# SCH_microprocessor-8085_2025-05-18.net
KiCad netlist of a schematic drawn in EasyEDA
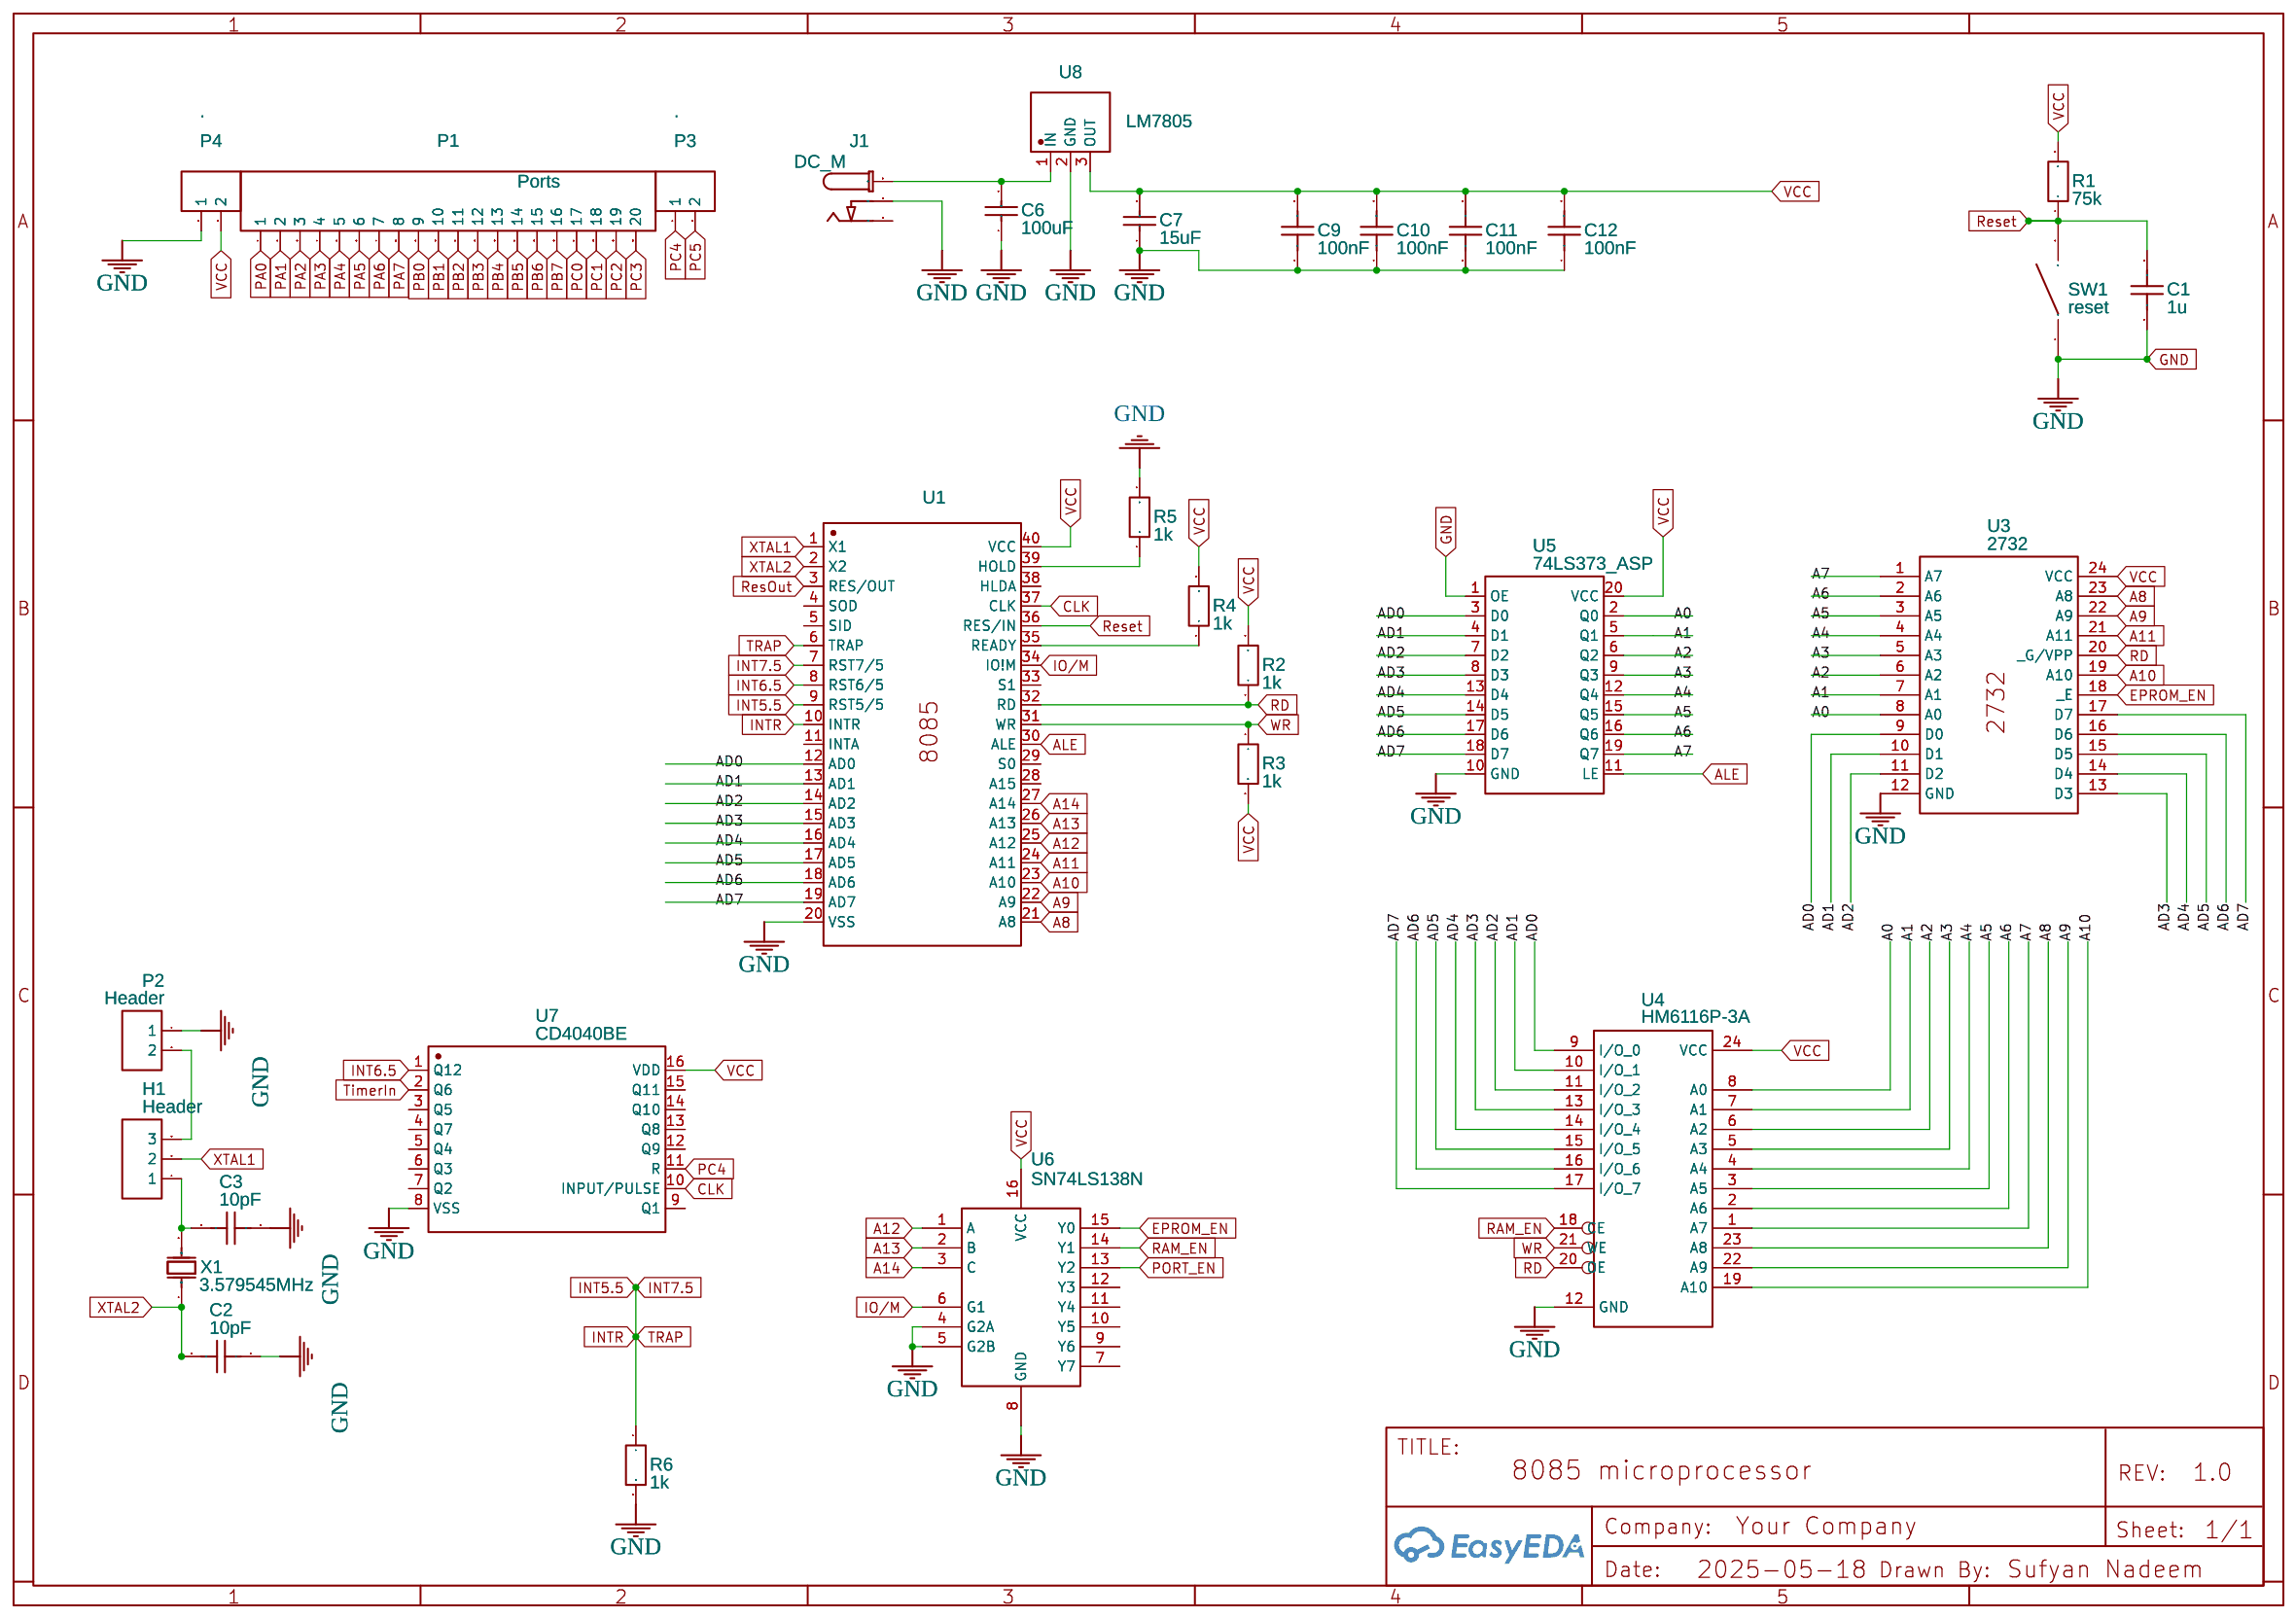
[diagram p0: schematic sheet]

(export (version "E")
  (design (tool "Eeschema 10.0.6"))
  (components
    (comp (ref "C1") (value "1u") (libsource (lib "") (part "Cap_RAD-0.1_US")))
    (comp (ref "C2")
      (value "10pF")
      (fields (field (name "Manufacturer Part") "CC4-0805N100 J500") (field (name "Manufacturer") "ReliaPro"))
      (libsource (lib "") (part "CC4-0805N100 J500"))
    )
    (comp (ref "C3")
      (value "10pF")
      (fields (field (name "Manufacturer Part") "CC4-0805N100 J500") (field (name "Manufacturer") "ReliaPro"))
      (libsource (lib "") (part "CC4-0805N100 J500"))
    )
    (comp (ref "C6")
      (value "100uF")
      (fields (field (name "Manufacturer Part") "Capacitor15nf100v") (field (name "Manufacturer") "ReliaPro"))
      (libsource (lib "") (part "CAPACITOR15NF100V"))
    )
    (comp (ref "C7")
      (value "15uF")
      (fields (field (name "Manufacturer Part") "Capacitor15nf100v") (field (name "Manufacturer") "ReliaPro"))
      (libsource (lib "") (part "CAPACITOR15NF100V"))
    )
    (comp (ref "C9")
      (value "100nF")
      (fields (field (name "Manufacturer Part") "CT4-0805B104K500F3") (field (name "Manufacturer") "FH"))
      (libsource (lib "") (part "CT4-0805B104K500F3"))
    )
    (comp (ref "C10")
      (value "100nF")
      (fields (field (name "Manufacturer Part") "CT4-0805B104K500F3") (field (name "Manufacturer") "FH"))
      (libsource (lib "") (part "CT4-0805B104K500F3"))
    )
    (comp (ref "C11")
      (value "100nF")
      (fields (field (name "Manufacturer Part") "CT4-0805B104K500F3") (field (name "Manufacturer") "FH"))
      (libsource (lib "") (part "CT4-0805B104K500F3"))
    )
    (comp (ref "C12")
      (value "100nF")
      (fields (field (name "Manufacturer Part") "CT4-0805B104K500F3") (field (name "Manufacturer") "FH"))
      (libsource (lib "") (part "CT4-0805B104K500F3"))
    )
    (comp (ref "H1")
      (value "Header")
      (fields (field (name "Manufacturer Part") "Header2.54mm 1*3P") (field (name "Manufacturer") "BOOMELE"))
      (libsource (lib "") (part "Unknown_50_-260"))
    )
    (comp (ref "J1") (value "DC_M") (libsource (lib "") (part "Unknown_410_-745")))
    (comp (ref "P1")
      (value "Ports")
      (fields
        (field (name "Manufacturer Part") "2.54mm 1*20P Female header")
        (field (name "Manufacturer") "BOOMELE")
      )
      (libsource (lib "") (part "Unknown_200_-740"))
    )
    (comp (ref "P2")
      (value "Header")
      (fields (field (name "Manufacturer Part") "2.54-1*2PFemale") (field (name "Manufacturer") "BOOMELE"))
      (libsource (lib "") (part "Header-Female-2.54_1x2"))
    )
    (comp (ref "P3")
      (value ".")
      (fields (field (name "Manufacturer Part") "2.54-1*2PFemale") (field (name "Manufacturer") "BOOMELE"))
      (libsource (lib "") (part "Unknown_320_-745"))
    )
    (comp (ref "P4")
      (value ".")
      (fields (field (name "Manufacturer Part") "2.54-1*2PFemale") (field (name "Manufacturer") "BOOMELE"))
      (libsource (lib "") (part "Unknown_80_-745"))
    )
    (comp (ref "R1") (value "75k") (libsource (lib "") (part "Res_AXIAL-0.3(1/8W)_EU")))
    (comp (ref "R2") (value "1k") (libsource (lib "") (part "Res_AXIAL-0.3(1/8W)_EU")))
    (comp (ref "R3") (value "1k") (libsource (lib "") (part "Res_AXIAL-0.3(1/8W)_EU_1")))
    (comp (ref "R4") (value "1k") (libsource (lib "") (part "Res_AXIAL-0.3(1/8W)_EU")))
    (comp (ref "R5") (value "1k") (libsource (lib "") (part "Res_AXIAL-0.3(1/8W)_EU")))
    (comp (ref "R6") (value "1k") (libsource (lib "") (part "Res_AXIAL-0.3(1/8W)_EU_1")))
    (comp (ref "SW1")
      (value "reset")
      (fields (field (name "Manufacturer Part") "EVQ22705R") (field (name "Manufacturer") "PANASONIC"))
      (libsource (lib "") (part "Unknown_1015_-700"))
    )
    (comp (ref "U1") (value "8085_ASP") (libsource (lib "") (part "Unknown_440_-475")))
    (comp (ref "U3") (value "2732") (libsource (lib "") (part "Unknown_945_-565")))
    (comp (ref "U4")
      (value "HM6116P-3A")
      (fields (field (name "Manufacturer Part") "HM6116P-3"))
      (libsource (lib "") (part "HM6116P-3A"))
    )
    (comp (ref "U5") (value "74LS373_ASP") (libsource (lib "") (part "Unknown_725_-555")))
    (comp (ref "U6")
      (value "SN74LS138N")
      (fields (field (name "Manufacturer") "Texas Instruments"))
      (libsource (lib "") (part "Unknown_490_-185"))
    )
    (comp (ref "U7")
      (value "CD4040BE")
      (fields (field (name "Manufacturer") "TI"))
      (libsource (lib "") (part "Unknown_250_-270"))
    )
    (comp (ref "U8")
      (value "LM7805")
      (fields
        (field (name "Manufacturer Part") "LM7805AL-TA3-T")
        (field (name "Manufacturer") "Unisonic Tech")
      )
      (libsource (lib "") (part "Unknown_515_-785"))
    )
    (comp (ref "X1")
      (value "3.579545MHz")
      (fields
        (field (name "Manufacturer Part") "XIHCELNANF-3.579545M")
        (field (name "Manufacturer") "TAITIEN Elec")
      )
      (libsource (lib "") (part "XIHCELNANF-3.579545M"))
    )
  )
  (nets
    (net (code "1") (name "/A0") (class "Default")
      (node (ref "U3") (pin "8") (pinfunction "A0_8") (pintype "unspecified"))
      (node (ref "U4") (pin "8") (pinfunction "A0_8") (pintype "input"))
      (node (ref "U5") (pin "2") (pinfunction "Q0_2") (pintype "unspecified"))
    )
    (net (code "2") (name "/A1") (class "Default")
      (node (ref "U3") (pin "7") (pinfunction "A1_7") (pintype "unspecified"))
      (node (ref "U4") (pin "7") (pinfunction "A1_7") (pintype "input"))
      (node (ref "U5") (pin "5") (pinfunction "Q1_5") (pintype "unspecified"))
    )
    (net (code "3") (name "/A2") (class "Default")
      (node (ref "U3") (pin "6") (pinfunction "A2_6") (pintype "unspecified"))
      (node (ref "U4") (pin "6") (pinfunction "A2_6") (pintype "input"))
      (node (ref "U5") (pin "6") (pinfunction "Q2_6") (pintype "unspecified"))
    )
    (net (code "4") (name "/A3") (class "Default")
      (node (ref "U3") (pin "5") (pinfunction "A3_5") (pintype "unspecified"))
      (node (ref "U4") (pin "5") (pinfunction "A3_5") (pintype "input"))
      (node (ref "U5") (pin "9") (pinfunction "Q3_9") (pintype "unspecified"))
    )
    (net (code "5") (name "/A4") (class "Default")
      (node (ref "U3") (pin "4") (pinfunction "A4_4") (pintype "unspecified"))
      (node (ref "U4") (pin "4") (pinfunction "A4_4") (pintype "input"))
      (node (ref "U5") (pin "12") (pinfunction "Q4_12") (pintype "unspecified"))
    )
    (net (code "6") (name "/A5") (class "Default")
      (node (ref "U3") (pin "3") (pinfunction "A5_3") (pintype "unspecified"))
      (node (ref "U4") (pin "3") (pinfunction "A5_3") (pintype "input"))
      (node (ref "U5") (pin "15") (pinfunction "Q5_15") (pintype "unspecified"))
    )
    (net (code "7") (name "/A6") (class "Default")
      (node (ref "U3") (pin "2") (pinfunction "A6_2") (pintype "unspecified"))
      (node (ref "U4") (pin "2") (pinfunction "A6_2") (pintype "input"))
      (node (ref "U5") (pin "16") (pinfunction "Q6_16") (pintype "unspecified"))
    )
    (net (code "8") (name "/A7") (class "Default")
      (node (ref "U3") (pin "1") (pinfunction "A7_1") (pintype "unspecified"))
      (node (ref "U4") (pin "1") (pinfunction "A7_1") (pintype "input"))
      (node (ref "U5") (pin "19") (pinfunction "Q7_19") (pintype "unspecified"))
    )
    (net (code "9") (name "/AD0") (class "Default")
      (node (ref "U1") (pin "12") (pinfunction "AD0_12") (pintype "unspecified"))
      (node (ref "U3") (pin "9") (pinfunction "D0_9") (pintype "unspecified"))
      (node (ref "U4") (pin "9") (pinfunction "I/O_0_9") (pintype "bidirectional"))
      (node (ref "U5") (pin "3") (pinfunction "D0_3") (pintype "unspecified"))
    )
    (net (code "10") (name "/AD1") (class "Default")
      (node (ref "U1") (pin "13") (pinfunction "AD1_13") (pintype "unspecified"))
      (node (ref "U3") (pin "10") (pinfunction "D1_10") (pintype "unspecified"))
      (node (ref "U4") (pin "10") (pinfunction "I/O_1_10") (pintype "bidirectional"))
      (node (ref "U5") (pin "4") (pinfunction "D1_4") (pintype "unspecified"))
    )
    (net (code "11") (name "/AD2") (class "Default")
      (node (ref "U1") (pin "14") (pinfunction "AD2_14") (pintype "unspecified"))
      (node (ref "U3") (pin "11") (pinfunction "D2_11") (pintype "unspecified"))
      (node (ref "U4") (pin "11") (pinfunction "I/O_2_11") (pintype "bidirectional"))
      (node (ref "U5") (pin "7") (pinfunction "D2_7") (pintype "unspecified"))
    )
    (net (code "12") (name "/AD3") (class "Default")
      (node (ref "U1") (pin "15") (pinfunction "AD3_15") (pintype "unspecified"))
      (node (ref "U3") (pin "13") (pinfunction "D3_13") (pintype "unspecified"))
      (node (ref "U4") (pin "13") (pinfunction "I/O_3_13") (pintype "bidirectional"))
      (node (ref "U5") (pin "8") (pinfunction "D3_8") (pintype "unspecified"))
    )
    (net (code "13") (name "/AD4") (class "Default")
      (node (ref "U1") (pin "16") (pinfunction "AD4_16") (pintype "unspecified"))
      (node (ref "U3") (pin "14") (pinfunction "D4_14") (pintype "unspecified"))
      (node (ref "U4") (pin "14") (pinfunction "I/O_4_14") (pintype "bidirectional"))
      (node (ref "U5") (pin "13") (pinfunction "D4_13") (pintype "unspecified"))
    )
    (net (code "14") (name "/AD5") (class "Default")
      (node (ref "U1") (pin "17") (pinfunction "AD5_17") (pintype "unspecified"))
      (node (ref "U3") (pin "15") (pinfunction "D5_15") (pintype "unspecified"))
      (node (ref "U4") (pin "15") (pinfunction "I/O_5_15") (pintype "bidirectional"))
      (node (ref "U5") (pin "14") (pinfunction "D5_14") (pintype "unspecified"))
    )
    (net (code "15") (name "/AD6") (class "Default")
      (node (ref "U1") (pin "18") (pinfunction "AD6_18") (pintype "unspecified"))
      (node (ref "U3") (pin "16") (pinfunction "D6_16") (pintype "unspecified"))
      (node (ref "U4") (pin "16") (pinfunction "I/O_6_16") (pintype "bidirectional"))
      (node (ref "U5") (pin "17") (pinfunction "D6_17") (pintype "unspecified"))
    )
    (net (code "16") (name "/AD7") (class "Default")
      (node (ref "U1") (pin "19") (pinfunction "AD7_19") (pintype "unspecified"))
      (node (ref "U3") (pin "17") (pinfunction "D7_17") (pintype "unspecified"))
      (node (ref "U4") (pin "17") (pinfunction "I/O_7_17") (pintype "bidirectional"))
      (node (ref "U5") (pin "18") (pinfunction "D7_18") (pintype "unspecified"))
    )
    (net (code "17") (name "A8") (class "Default")
      (node (ref "U1") (pin "21") (pinfunction "A8_21") (pintype "unspecified"))
      (node (ref "U3") (pin "23") (pinfunction "A8_23") (pintype "unspecified"))
      (node (ref "U4") (pin "23") (pinfunction "A8_23") (pintype "input"))
    )
    (net (code "18") (name "A9") (class "Default")
      (node (ref "U1") (pin "22") (pinfunction "A9_22") (pintype "unspecified"))
      (node (ref "U3") (pin "22") (pinfunction "A9_22") (pintype "unspecified"))
      (node (ref "U4") (pin "22") (pinfunction "A9_22") (pintype "input"))
    )
    (net (code "19") (name "A10") (class "Default")
      (node (ref "U1") (pin "23") (pinfunction "A10_23") (pintype "unspecified"))
      (node (ref "U3") (pin "19") (pinfunction "A10_19") (pintype "unspecified"))
      (node (ref "U4") (pin "19") (pinfunction "A10_19") (pintype "input"))
    )
    (net (code "20") (name "A11") (class "Default")
      (node (ref "U1") (pin "24") (pinfunction "A11_24") (pintype "unspecified"))
      (node (ref "U3") (pin "21") (pinfunction "A11_21") (pintype "unspecified"))
    )
    (net (code "21") (name "A12") (class "Default")
      (node (ref "U1") (pin "25") (pinfunction "A12_25") (pintype "unspecified"))
      (node (ref "U6") (pin "1") (pinfunction "A_1") (pintype "unspecified"))
    )
    (net (code "22") (name "A13") (class "Default")
      (node (ref "U1") (pin "26") (pinfunction "A13_26") (pintype "unspecified"))
      (node (ref "U6") (pin "2") (pinfunction "B_2") (pintype "unspecified"))
    )
    (net (code "23") (name "A14") (class "Default")
      (node (ref "U1") (pin "27") (pinfunction "A14_27") (pintype "unspecified"))
      (node (ref "U6") (pin "3") (pinfunction "C_3") (pintype "unspecified"))
    )
    (net (code "24") (name "ALE") (class "Default")
      (node (ref "U1") (pin "30") (pinfunction "ALE_30") (pintype "unspecified"))
      (node (ref "U5") (pin "11") (pinfunction "LE_11") (pintype "unspecified"))
    )
    (net (code "25") (name "CLK") (class "Default")
      (node (ref "U1") (pin "37") (pinfunction "CLK_37") (pintype "unspecified"))
      (node (ref "U7") (pin "10") (pinfunction "INPUT/PULSE_10") (pintype "unspecified"))
    )
    (net (code "26") (name "EPROM_EN") (class "Default")
      (node (ref "U3") (pin "18") (pinfunction "_E_18") (pintype "unspecified"))
      (node (ref "U6") (pin "15") (pinfunction "Y0_15") (pintype "unspecified"))
    )
    (net (code "27") (name "GND") (class "Default")
      (node (ref "C1") (pin "1") (pinfunction "1_1") (pintype "unspecified"))
      (node (ref "C10") (pin "1") (pinfunction "1_1") (pintype "unspecified"))
      (node (ref "C11") (pin "1") (pinfunction "1_1") (pintype "unspecified"))
      (node (ref "C12") (pin "1") (pinfunction "1_1") (pintype "unspecified"))
      (node (ref "C2") (pin "1") (pinfunction "1_1") (pintype "unspecified"))
      (node (ref "C3") (pin "1") (pinfunction "1_1") (pintype "unspecified"))
      (node (ref "C6") (pin "1") (pinfunction "1_1") (pintype "input"))
      (node (ref "C7") (pin "1") (pinfunction "1_1") (pintype "input"))
      (node (ref "C9") (pin "1") (pinfunction "1_1") (pintype "unspecified"))
      (node (ref "J1") (pin "P2") (pinfunction "P3_P2") (pintype "unspecified"))
      (node (ref "P2") (pin "1") (pinfunction "1_1") (pintype "input"))
      (node (ref "P4") (pin "1") (pinfunction "1_1") (pintype "input"))
      (node (ref "R5") (pin "2") (pinfunction "2_2") (pintype "unspecified"))
      (node (ref "R6") (pin "2") (pinfunction "2_2") (pintype "unspecified"))
      (node (ref "SW1") (pin "1") (pinfunction "1_1") (pintype "input"))
      (node (ref "U1") (pin "20") (pinfunction "VSS_20") (pintype "unspecified"))
      (node (ref "U3") (pin "12") (pinfunction "GND_12") (pintype "unspecified"))
      (node (ref "U4") (pin "12") (pinfunction "GND_12") (pintype "passive"))
      (node (ref "U5") (pin "1") (pinfunction "OE_1") (pintype "unspecified"))
      (node (ref "U5") (pin "10") (pinfunction "GND_10") (pintype "unspecified"))
      (node (ref "U6") (pin "4") (pinfunction "G2A_4") (pintype "unspecified"))
      (node (ref "U6") (pin "5") (pinfunction "G2B_5") (pintype "unspecified"))
      (node (ref "U6") (pin "8") (pinfunction "GND_8") (pintype "unspecified"))
      (node (ref "U7") (pin "8") (pinfunction "VSS_8") (pintype "unspecified"))
      (node (ref "U8") (pin "2") (pinfunction "GND_2") (pintype "unspecified"))
    )
    (net (code "28") (name "INT5.5") (class "Default")
      (node (ref "R6") (pin "1") (pinfunction "1_1") (pintype "unspecified"))
      (node (ref "U1") (pin "10") (pinfunction "INTR_10") (pintype "unspecified"))
      (node (ref "U1") (pin "6") (pinfunction "TRAP_6") (pintype "unspecified"))
      (node (ref "U1") (pin "7") (pinfunction "RST7/5_7") (pintype "unspecified"))
      (node (ref "U1") (pin "9") (pinfunction "RST5/5_9") (pintype "unspecified"))
    )
    (net (code "29") (name "INT6.5") (class "Default")
      (node (ref "U1") (pin "8") (pinfunction "RST6/5_8") (pintype "unspecified"))
      (node (ref "U7") (pin "1") (pinfunction "Q12_1") (pintype "unspecified"))
    )
    (net (code "30") (name "IO{slash}M") (class "Default")
      (node (ref "U1") (pin "34") (pinfunction "IO!M_34") (pintype "unspecified"))
      (node (ref "U6") (pin "6") (pinfunction "G1_6") (pintype "unspecified"))
    )
    (net (code "31") (name "Net-(H1-Pad3)") (class "Default")
      (node (ref "H1") (pin "3") (pinfunction "3_3") (pintype "input"))
      (node (ref "P2") (pin "2") (pinfunction "2_2") (pintype "input"))
    )
    (net (code "32") (name "Net-(U1-HOLD)") (class "Default")
      (node (ref "R5") (pin "1") (pinfunction "1_1") (pintype "unspecified"))
      (node (ref "U1") (pin "39") (pinfunction "HOLD_39") (pintype "unspecified"))
    )
    (net (code "33") (name "Net-(U1-READY)") (class "Default")
      (node (ref "R4") (pin "1") (pinfunction "1_1") (pintype "unspecified"))
      (node (ref "U1") (pin "35") (pinfunction "READY_35") (pintype "unspecified"))
    )
    (net (code "34") (name "Net-(U8-IN)") (class "Default")
      (node (ref "C6") (pin "2") (pinfunction "2_2") (pintype "input"))
      (node (ref "J1") (pin "P1") (pinfunction "P1_P1") (pintype "unspecified"))
      (node (ref "U8") (pin "1") (pinfunction "IN_1") (pintype "unspecified"))
    )
    (net (code "35") (name "Net-(X1-OSC2)") (class "Default")
      (node (ref "C3") (pin "2") (pinfunction "2_2") (pintype "unspecified"))
      (node (ref "H1") (pin "1") (pinfunction "1_1") (pintype "input"))
      (node (ref "X1") (pin "2") (pinfunction "OSC2_2") (pintype "input"))
    )
    (net (code "36") (name "PA0") (class "Default")
      (node (ref "P1") (pin "1") (pinfunction "1_1") (pintype "input"))
    )
    (net (code "37") (name "PA1") (class "Default")
      (node (ref "P1") (pin "2") (pinfunction "2_2") (pintype "input"))
    )
    (net (code "38") (name "PA2") (class "Default")
      (node (ref "P1") (pin "3") (pinfunction "3_3") (pintype "input"))
    )
    (net (code "39") (name "PA3") (class "Default")
      (node (ref "P1") (pin "4") (pinfunction "4_4") (pintype "input"))
    )
    (net (code "40") (name "PA4") (class "Default")
      (node (ref "P1") (pin "5") (pinfunction "5_5") (pintype "input"))
    )
    (net (code "41") (name "PA5") (class "Default")
      (node (ref "P1") (pin "6") (pinfunction "6_6") (pintype "input"))
    )
    (net (code "42") (name "PA6") (class "Default")
      (node (ref "P1") (pin "7") (pinfunction "7_7") (pintype "input"))
    )
    (net (code "43") (name "PA7") (class "Default")
      (node (ref "P1") (pin "8") (pinfunction "8_8") (pintype "input"))
    )
    (net (code "44") (name "PB0") (class "Default")
      (node (ref "P1") (pin "9") (pinfunction "9_9") (pintype "input"))
    )
    (net (code "45") (name "PB1") (class "Default")
      (node (ref "P1") (pin "10") (pinfunction "10_10") (pintype "input"))
    )
    (net (code "46") (name "PB2") (class "Default")
      (node (ref "P1") (pin "11") (pinfunction "11_11") (pintype "input"))
    )
    (net (code "47") (name "PB3") (class "Default")
      (node (ref "P1") (pin "12") (pinfunction "12_12") (pintype "input"))
    )
    (net (code "48") (name "PB4") (class "Default")
      (node (ref "P1") (pin "13") (pinfunction "13_13") (pintype "input"))
    )
    (net (code "49") (name "PB5") (class "Default")
      (node (ref "P1") (pin "14") (pinfunction "14_14") (pintype "input"))
    )
    (net (code "50") (name "PB6") (class "Default")
      (node (ref "P1") (pin "15") (pinfunction "15_15") (pintype "input"))
    )
    (net (code "51") (name "PB7") (class "Default")
      (node (ref "P1") (pin "16") (pinfunction "16_16") (pintype "input"))
    )
    (net (code "52") (name "PC0") (class "Default")
      (node (ref "P1") (pin "17") (pinfunction "17_17") (pintype "input"))
    )
    (net (code "53") (name "PC1") (class "Default")
      (node (ref "P1") (pin "18") (pinfunction "18_18") (pintype "input"))
    )
    (net (code "54") (name "PC2") (class "Default")
      (node (ref "P1") (pin "19") (pinfunction "19_19") (pintype "input"))
    )
    (net (code "55") (name "PC3") (class "Default")
      (node (ref "P1") (pin "20") (pinfunction "20_20") (pintype "input"))
    )
    (net (code "56") (name "PC4") (class "Default")
      (node (ref "P3") (pin "1") (pinfunction "1_1") (pintype "input"))
      (node (ref "U7") (pin "11") (pinfunction "R_11") (pintype "unspecified"))
    )
    (net (code "57") (name "PC5") (class "Default")
      (node (ref "P3") (pin "2") (pinfunction "2_2") (pintype "input"))
    )
    (net (code "58") (name "PORT_EN") (class "Default")
      (node (ref "U6") (pin "13") (pinfunction "Y2_13") (pintype "unspecified"))
    )
    (net (code "59") (name "RAM_EN") (class "Default")
      (node (ref "U4") (pin "18") (pinfunction "CE_18") (pintype "input"))
      (node (ref "U6") (pin "14") (pinfunction "Y1_14") (pintype "unspecified"))
    )
    (net (code "60") (name "RD") (class "Default")
      (node (ref "R2") (pin "1") (pinfunction "1_1") (pintype "unspecified"))
      (node (ref "U1") (pin "32") (pinfunction "RD_32") (pintype "unspecified"))
      (node (ref "U3") (pin "20") (pinfunction "_G/VPP_20") (pintype "unspecified"))
      (node (ref "U4") (pin "20") (pinfunction "OE_20") (pintype "input"))
    )
    (net (code "61") (name "ResOut") (class "Default")
      (node (ref "U1") (pin "3") (pinfunction "RES/OUT_3") (pintype "unspecified"))
    )
    (net (code "62") (name "Reset") (class "Default")
      (node (ref "C1") (pin "2") (pinfunction "2_2") (pintype "unspecified"))
      (node (ref "R1") (pin "1") (pinfunction "1_1") (pintype "unspecified"))
      (node (ref "SW1") (pin "2") (pinfunction "2_2") (pintype "input"))
      (node (ref "U1") (pin "36") (pinfunction "RES/IN_36") (pintype "unspecified"))
    )
    (net (code "63") (name "TimerIn") (class "Default")
      (node (ref "U7") (pin "2") (pinfunction "Q6_2") (pintype "unspecified"))
    )
    (net (code "64") (name "VCC") (class "Default")
      (node (ref "C10") (pin "2") (pinfunction "2_2") (pintype "unspecified"))
      (node (ref "C11") (pin "2") (pinfunction "2_2") (pintype "unspecified"))
      (node (ref "C12") (pin "2") (pinfunction "2_2") (pintype "unspecified"))
      (node (ref "C7") (pin "2") (pinfunction "2_2") (pintype "input"))
      (node (ref "C9") (pin "2") (pinfunction "2_2") (pintype "unspecified"))
      (node (ref "P4") (pin "2") (pinfunction "2_2") (pintype "input"))
      (node (ref "R1") (pin "2") (pinfunction "2_2") (pintype "unspecified"))
      (node (ref "R2") (pin "2") (pinfunction "2_2") (pintype "unspecified"))
      (node (ref "R3") (pin "2") (pinfunction "2_2") (pintype "unspecified"))
      (node (ref "R4") (pin "2") (pinfunction "2_2") (pintype "unspecified"))
      (node (ref "U1") (pin "40") (pinfunction "VCC_40") (pintype "unspecified"))
      (node (ref "U3") (pin "24") (pinfunction "VCC_24") (pintype "unspecified"))
      (node (ref "U4") (pin "24") (pinfunction "VCC_24") (pintype "passive"))
      (node (ref "U5") (pin "20") (pinfunction "VCC_20") (pintype "unspecified"))
      (node (ref "U6") (pin "16") (pinfunction "VCC_16") (pintype "unspecified"))
      (node (ref "U7") (pin "16") (pinfunction "VDD_16") (pintype "unspecified"))
      (node (ref "U8") (pin "3") (pinfunction "OUT_3") (pintype "unspecified"))
    )
    (net (code "65") (name "WR") (class "Default")
      (node (ref "R3") (pin "1") (pinfunction "1_1") (pintype "unspecified"))
      (node (ref "U1") (pin "31") (pinfunction "WR_31") (pintype "unspecified"))
      (node (ref "U4") (pin "21") (pinfunction "WE_21") (pintype "input"))
    )
    (net (code "66") (name "XTAL1") (class "Default")
      (node (ref "H1") (pin "2") (pinfunction "2_2") (pintype "input"))
      (node (ref "U1") (pin "1") (pinfunction "X1_1") (pintype "unspecified"))
    )
    (net (code "67") (name "XTAL2") (class "Default")
      (node (ref "C2") (pin "2") (pinfunction "2_2") (pintype "unspecified"))
      (node (ref "U1") (pin "2") (pinfunction "X2_2") (pintype "unspecified"))
      (node (ref "X1") (pin "1") (pinfunction "OSC1_1") (pintype "input"))
    )
    (net (code "68") (name "unconnected-(J1-P2-PadP3)") (class "Default")
      (node (ref "J1") (pin "P3") (pinfunction "P2_P3") (pintype "unspecified"))
    )
    (net (code "69") (name "unconnected-(U1-A15-Pad28)") (class "Default")
      (node (ref "U1") (pin "28") (pinfunction "A15_28") (pintype "unspecified"))
    )
    (net (code "70") (name "unconnected-(U1-HLDA-Pad38)") (class "Default")
      (node (ref "U1") (pin "38") (pinfunction "HLDA_38") (pintype "unspecified"))
    )
    (net (code "71") (name "unconnected-(U1-INTA-Pad11)") (class "Default")
      (node (ref "U1") (pin "11") (pinfunction "INTA_11") (pintype "unspecified"))
    )
    (net (code "72") (name "unconnected-(U1-S0-Pad29)") (class "Default")
      (node (ref "U1") (pin "29") (pinfunction "S0_29") (pintype "unspecified"))
    )
    (net (code "73") (name "unconnected-(U1-S1-Pad33)") (class "Default")
      (node (ref "U1") (pin "33") (pinfunction "S1_33") (pintype "unspecified"))
    )
    (net (code "74") (name "unconnected-(U1-SID-Pad5)") (class "Default")
      (node (ref "U1") (pin "5") (pinfunction "SID_5") (pintype "unspecified"))
    )
    (net (code "75") (name "unconnected-(U1-SOD-Pad4)") (class "Default")
      (node (ref "U1") (pin "4") (pinfunction "SOD_4") (pintype "unspecified"))
    )
    (net (code "76") (name "unconnected-(U6-Y3-Pad12)") (class "Default")
      (node (ref "U6") (pin "12") (pinfunction "Y3_12") (pintype "unspecified"))
    )
    (net (code "77") (name "unconnected-(U6-Y4-Pad11)") (class "Default")
      (node (ref "U6") (pin "11") (pinfunction "Y4_11") (pintype "unspecified"))
    )
    (net (code "78") (name "unconnected-(U6-Y5-Pad10)") (class "Default")
      (node (ref "U6") (pin "10") (pinfunction "Y5_10") (pintype "unspecified"))
    )
    (net (code "79") (name "unconnected-(U6-Y6-Pad9)") (class "Default")
      (node (ref "U6") (pin "9") (pinfunction "Y6_9") (pintype "unspecified"))
    )
    (net (code "80") (name "unconnected-(U6-Y7-Pad7)") (class "Default")
      (node (ref "U6") (pin "7") (pinfunction "Y7_7") (pintype "unspecified"))
    )
    (net (code "81") (name "unconnected-(U7-Q1-Pad9)") (class "Default")
      (node (ref "U7") (pin "9") (pinfunction "Q1_9") (pintype "unspecified"))
    )
    (net (code "82") (name "unconnected-(U7-Q2-Pad7)") (class "Default")
      (node (ref "U7") (pin "7") (pinfunction "Q2_7") (pintype "unspecified"))
    )
    (net (code "83") (name "unconnected-(U7-Q3-Pad6)") (class "Default")
      (node (ref "U7") (pin "6") (pinfunction "Q3_6") (pintype "unspecified"))
    )
    (net (code "84") (name "unconnected-(U7-Q4-Pad5)") (class "Default")
      (node (ref "U7") (pin "5") (pinfunction "Q4_5") (pintype "unspecified"))
    )
    (net (code "85") (name "unconnected-(U7-Q5-Pad3)") (class "Default")
      (node (ref "U7") (pin "3") (pinfunction "Q5_3") (pintype "unspecified"))
    )
    (net (code "86") (name "unconnected-(U7-Q7-Pad4)") (class "Default")
      (node (ref "U7") (pin "4") (pinfunction "Q7_4") (pintype "unspecified"))
    )
    (net (code "87") (name "unconnected-(U7-Q8-Pad13)") (class "Default")
      (node (ref "U7") (pin "13") (pinfunction "Q8_13") (pintype "unspecified"))
    )
    (net (code "88") (name "unconnected-(U7-Q9-Pad12)") (class "Default")
      (node (ref "U7") (pin "12") (pinfunction "Q9_12") (pintype "unspecified"))
    )
    (net (code "89") (name "unconnected-(U7-Q10-Pad14)") (class "Default")
      (node (ref "U7") (pin "14") (pinfunction "Q10_14") (pintype "unspecified"))
    )
    (net (code "90") (name "unconnected-(U7-Q11-Pad15)") (class "Default")
      (node (ref "U7") (pin "15") (pinfunction "Q11_15") (pintype "unspecified"))
    )
  )
)
